# Control.net
KiCad netlist of a schematic drawn in Altium Designer
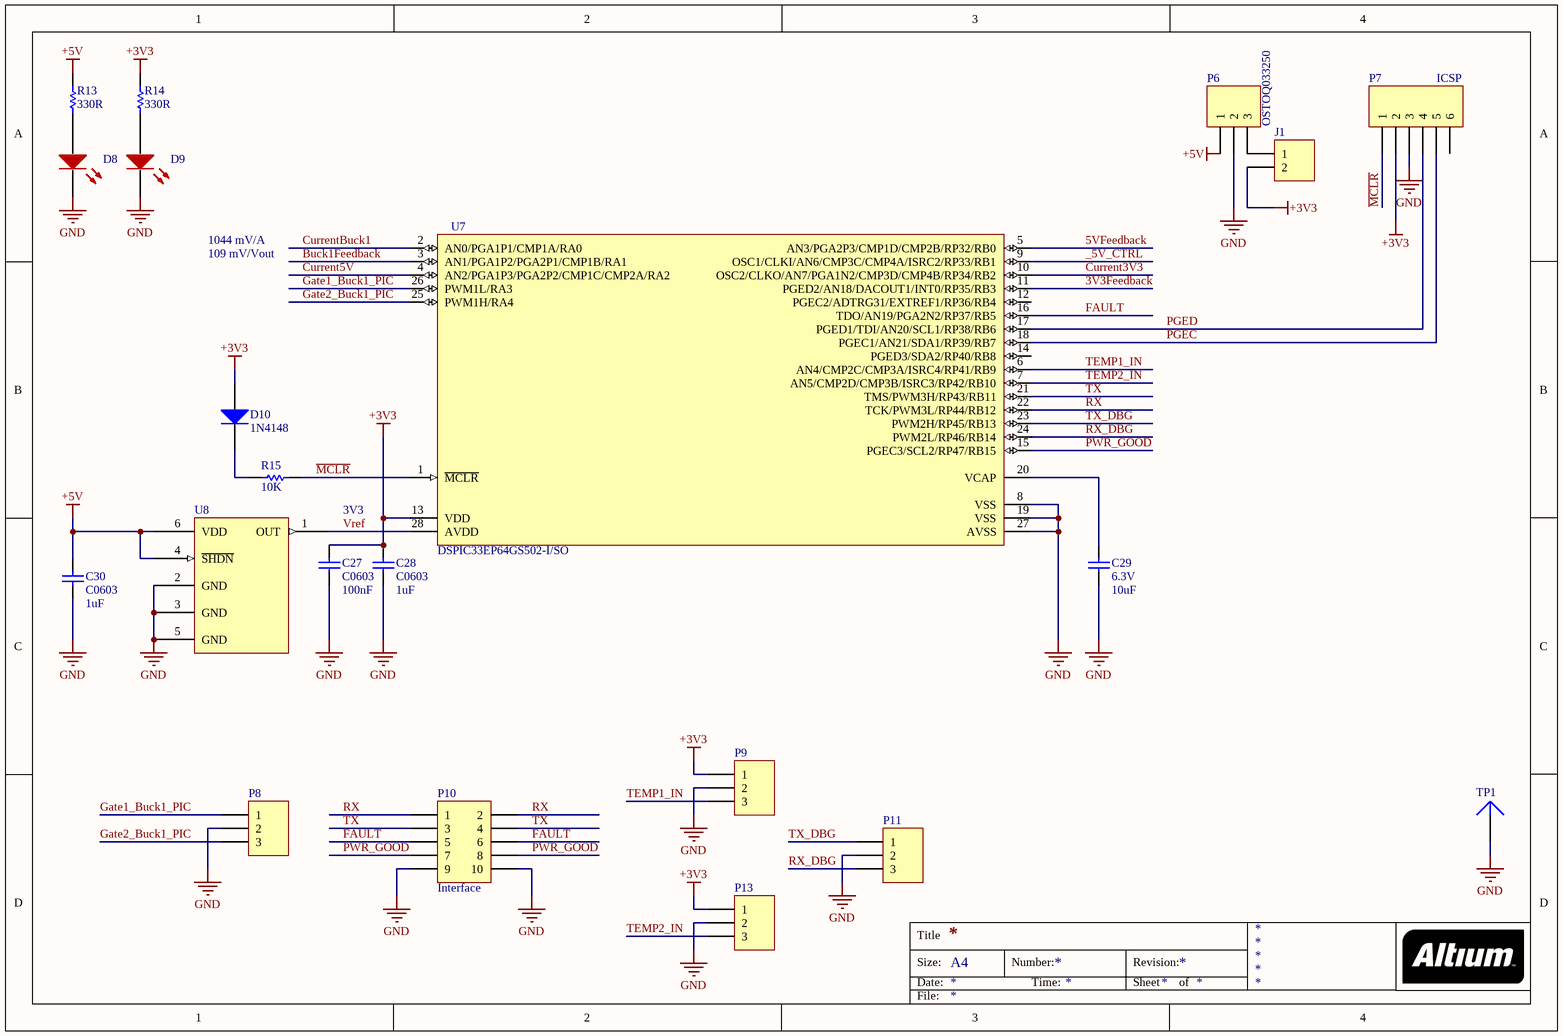
[diagram p0: Control.SchDoc]

(export (version "E")
  (design (tool "Eeschema 10.0.6"))
  (components
    (comp (ref "C27")
      (value "C0603")
      (footprint "0603")
      (description "C1608X7R1C105K X7R")
      (fields (field (name "ALTIUM_VALUE") "100nF") (field (name "PUBLISHER") "Altium Limited"))
      (libsource (lib "KEMET Chip Capacitor") (part "C0603"))
    )
    (comp (ref "C28")
      (value "C0603")
      (footprint "0603")
      (description "C1608X7R1C105K X7R")
      (fields (field (name "ALTIUM_VALUE") "1uF") (field (name "PUBLISHER") "Altium Limited"))
      (libsource (lib "KEMET Chip Capacitor") (part "C0603"))
    )
    (comp (ref "C29")
      (value "6.3V")
      (footprint "C0805")
      (description "Ceramic Chip Capacitor - MIL-PRF-55681")
      (fields (field (name "ALTIUM_VALUE") "10uF") (field (name "PUBLISHER") "Altium Limited"))
      (libsource (lib "KEMET Chip Capacitor") (part "CDR01"))
    )
    (comp (ref "C30")
      (value "C0603")
      (footprint "0603")
      (description "C1608X7R1C105K X7R")
      (fields (field (name "ALTIUM_VALUE") "1uF") (field (name "PUBLISHER") "Altium Limited"))
      (libsource (lib "KEMET Chip Capacitor") (part "C0603"))
    )
    (comp (ref "D8")
      (value "15-21SURC/S530-A3/TR8")
      (footprint "15-21SURC/S530-A3/TR8")
      (description "15-21SURC/S530-A3/TR8 led smd 0805 red")
      (libsource (lib "NXT") (part "15-21SURC/S530-A3/TR8 led smd 0805 red"))
    )
    (comp (ref "D9")
      (value "15-21SURC/S530-A3/TR8")
      (footprint "15-21SURC/S530-A3/TR8")
      (description "15-21SURC/S530-A3/TR8 led smd 0805 red")
      (libsource (lib "NXT") (part "15-21SURC/S530-A3/TR8 led smd 0805 red"))
    )
    (comp (ref "D10")
      (value "1N4148")
      (footprint "Philips Discrete Diode - Switching:SOD80C")
      (description "High Conductance Fast Diode")
      (fields (field (name "PUBLISHER") "Altium Limited"))
      (libsource (lib "FSC Discrete Diode") (part "1N4148"))
    )
    (comp (ref "J1")
      (value "Header 2")
      (footprint "My_1X02")
      (description "Header, 2-Pin")
      (fields (field (name "PUBLISHER") "Altium Limited"))
      (libsource (lib "Mylib") (part "Header 2"))
    )
    (comp (ref "P6")
      (value "XY2500R-F 3P")
      (footprint "OSTOQ033250")
      (description "HEADER 3P P/CI 90gra VERDE P=3.81MM XY2500R-F")
      (fields
        (field (name "MANUFACTURER") "On Shore Technology Inc.")
        (field (name "MANUFACTURER PART NUMBER") "OSTOQ033250")
      )
      (libsource (lib "NXT - Connectors") (part "XY2500R-F 3P"))
    )
    (comp (ref "P7")
      (value "ICSP")
      (footprint "My_1X06")
      (description "Header, 6-Pin")
      (fields (field (name "PUBLISHER") "Altium Limited"))
      (libsource (lib "Mylib") (part "Header 6"))
    )
    (comp (ref "P8")
      (value "Header 3")
      (footprint "My_1X03")
      (description "Header, 3-Pin")
      (fields (field (name "PUBLISHER") "Altium Limited"))
      (libsource (lib "Mylib") (part "Header 3"))
    )
    (comp (ref "P9")
      (value "Header 3")
      (footprint "My_1X03")
      (description "Header, 3-Pin")
      (fields (field (name "PUBLISHER") "Altium Limited"))
      (libsource (lib "Mylib") (part "Header 3"))
    )
    (comp (ref "P10")
      (value "Interface")
      (footprint "HDR2X5")
      (description "Header, 5-Pin, Dual row")
      (fields (field (name "PUBLISHER") "Altium Limited"))
      (libsource (lib "Miscellaneous Connectors") (part "Header 5X2"))
    )
    (comp (ref "P11")
      (value "Header 3")
      (footprint "My_1X03")
      (description "Header, 3-Pin")
      (fields (field (name "PUBLISHER") "Altium Limited"))
      (libsource (lib "Mylib") (part "Header 3"))
    )
    (comp (ref "P13")
      (value "Header 3")
      (footprint "My_1X03")
      (description "Header, 3-Pin")
      (fields (field (name "PUBLISHER") "Altium Limited"))
      (libsource (lib "Mylib") (part "Header 3"))
    )
    (comp (ref "R13")
      (value "330R")
      (footprint "8RB-1206")
      (fields (field (name "Comment") "SMD") (field (name "PUBLISHER") "Altium Limited"))
      (libsource (lib "Panasonic Resistor") (part "ERJ8BQ"))
    )
    (comp (ref "R14")
      (value "330R")
      (footprint "8RB-1206")
      (fields (field (name "Comment") "SMD") (field (name "PUBLISHER") "Altium Limited"))
      (libsource (lib "Panasonic Resistor") (part "ERJ8BQ"))
    )
    (comp (ref "R15")
      (value "10K")
      (footprint "ERA-0603")
      (fields (field (name "PUBLISHER") "Altium Limited"))
      (libsource (lib "Panasonic Resistor") (part "ERA3Y"))
    )
    (comp (ref "TP1")
      (value "~")
      (footprint "PIN1")
      (description "Plug")
      (fields (field (name "PUBLISHER") "Altium Limited"))
      (libsource (lib "Miscellaneous Connectors") (part "Plug"))
    )
    (comp (ref "U7")
      (value "DSPIC33EP64GS502")
      (footprint "MCHP-SOIC-SO28_N")
      (description "dsPIC dsPIC™ 33EP Microcontroller IC 16-Bit 70 MIPs 64KB (64K x 8) FLASH 28-SOIC")
      (fields
        (field (name "MANUFACTURER") "Microchip Technology")
        (field (name "MANUFACTURER PART NUMBER") "DSPIC33EP64GS502-I/SO")
      )
      (libsource (lib "NXT - IC") (part "DSPIC33EP64GS502"))
    )
    (comp (ref "U8")
      (value "MCP1501T")
      (footprint "SOT-23-6")
      (description "Series Voltage Reference IC ±0.08% 20mA SOT-23-6")
      (libsource (lib "NXT - IC") (part "MCP1501T"))
    )
  )
  (nets
    (net (code "1") (name "+3V3") (class "Default")
      (node (ref "C27") (pin "1") (pinfunction "1_1") (pintype "passive"))
      (node (ref "C28") (pin "1") (pinfunction "1_1") (pintype "passive"))
      (node (ref "D10") (pin "1") (pinfunction "A_1") (pintype "passive"))
      (node (ref "J1") (pin "2") (pinfunction "2_2") (pintype "passive"))
      (node (ref "P13") (pin "1") (pinfunction "1_1") (pintype "passive"))
      (node (ref "P7") (pin "2") (pinfunction "2_2") (pintype "passive"))
      (node (ref "P9") (pin "1") (pinfunction "1_1") (pintype "passive"))
      (node (ref "R14") (pin "1") (pinfunction "1_1") (pintype "passive"))
      (node (ref "U7") (pin "13") (pinfunction "VDD_13") (pintype "power_in"))
    )
    (net (code "2") (name "+5V") (class "Default")
      (node (ref "C30") (pin "1") (pinfunction "1_1") (pintype "passive"))
      (node (ref "P6") (pin "1") (pinfunction "1_1") (pintype "passive"))
      (node (ref "R13") (pin "1") (pinfunction "1_1") (pintype "passive"))
      (node (ref "U8") (pin "4") (pinfunction "~{SHDN}_4") (pintype "input"))
      (node (ref "U8") (pin "6") (pinfunction "VDD_6") (pintype "power_in"))
    )
    (net (code "3") (name "/3V3Feedback") (class "Default")
      (node (ref "U7") (pin "11") (pinfunction "PGED2/AN18/DACOUT1/INT0/RP35/RB3_11") (pintype "bidirectional"))
    )
    (net (code "4") (name "/5VFeedback") (class "Default")
      (node (ref "U7") (pin "5") (pinfunction "AN3/PGA2P3/CMP1D/CMP2B/RP32/RB0_5") (pintype "bidirectional"))
    )
    (net (code "5") (name "/Buck1Feedback") (class "Default")
      (node (ref "U7") (pin "3") (pinfunction "AN1/PGA1P2/PGA2P1/CMP1B/RA1_3") (pintype "bidirectional"))
    )
    (net (code "6") (name "/Current3V3") (class "Default")
      (node (ref "U7") (pin "10") (pinfunction "OSC2/CLKO/AN7/PGA1N2/CMP3D/CMP4B/RP34/RB2_10") (pintype "bidirectional"))
    )
    (net (code "7") (name "/Current5V") (class "Default")
      (node (ref "U7") (pin "4") (pinfunction "AN2/PGA1P3/PGA2P2/CMP1C/CMP2A/RA2_4") (pintype "bidirectional"))
    )
    (net (code "8") (name "/CurrentBuck1") (class "Default")
      (node (ref "U7") (pin "2") (pinfunction "AN0/PGA1P1/CMP1A/RA0_2") (pintype "bidirectional"))
    )
    (net (code "9") (name "/FAULT") (class "Default")
      (node (ref "P10") (pin "5") (pinfunction "5_5") (pintype "passive"))
      (node (ref "P10") (pin "6") (pinfunction "6_6") (pintype "passive"))
      (node (ref "U7") (pin "16") (pinfunction "TDO/AN19/PGA2N2/RP37/RB5_16") (pintype "bidirectional"))
    )
    (net (code "10") (name "/Gate1_Buck1_PIC") (class "Default")
      (node (ref "P8") (pin "1") (pinfunction "1_1") (pintype "passive"))
      (node (ref "U7") (pin "26") (pinfunction "PWM1L/RA3_26") (pintype "bidirectional"))
    )
    (net (code "11") (name "/Gate2_Buck1_PIC") (class "Default")
      (node (ref "P8") (pin "3") (pinfunction "3_3") (pintype "passive"))
      (node (ref "U7") (pin "25") (pinfunction "PWM1H/RA4_25") (pintype "bidirectional"))
    )
    (net (code "12") (name "/PGEC") (class "Default")
      (node (ref "P7") (pin "5") (pinfunction "5_5") (pintype "passive"))
      (node (ref "U7") (pin "18") (pinfunction "PGEC1/AN21/SDA1/RP39/RB7_18") (pintype "bidirectional"))
    )
    (net (code "13") (name "/PGED") (class "Default")
      (node (ref "P7") (pin "4") (pinfunction "4_4") (pintype "passive"))
      (node (ref "U7") (pin "17") (pinfunction "PGED1/TDI/AN20/SCL1/RP38/RB6_17") (pintype "bidirectional"))
    )
    (net (code "14") (name "/PWR_GOOD") (class "Default")
      (node (ref "P10") (pin "7") (pinfunction "7_7") (pintype "passive"))
      (node (ref "P10") (pin "8") (pinfunction "8_8") (pintype "passive"))
      (node (ref "U7") (pin "15") (pinfunction "PGEC3/SCL2/RP47/RB15_15") (pintype "bidirectional"))
    )
    (net (code "15") (name "/RX") (class "Default")
      (node (ref "P10") (pin "1") (pinfunction "1_1") (pintype "passive"))
      (node (ref "P10") (pin "2") (pinfunction "2_2") (pintype "passive"))
      (node (ref "U7") (pin "22") (pinfunction "TCK/PWM3L/RP44/RB12_22") (pintype "bidirectional"))
    )
    (net (code "16") (name "/RX_DBG") (class "Default")
      (node (ref "P11") (pin "3") (pinfunction "3_3") (pintype "passive"))
      (node (ref "U7") (pin "24") (pinfunction "PWM2L/RP46/RB14_24") (pintype "bidirectional"))
    )
    (net (code "17") (name "/TEMP1_IN") (class "Default")
      (node (ref "P9") (pin "3") (pinfunction "3_3") (pintype "passive"))
      (node (ref "U7") (pin "6") (pinfunction "AN4/CMP2C/CMP3A/ISRC4/RP41/RB9_6") (pintype "bidirectional"))
    )
    (net (code "18") (name "/TEMP2_IN") (class "Default")
      (node (ref "P13") (pin "3") (pinfunction "3_3") (pintype "passive"))
      (node (ref "U7") (pin "7") (pinfunction "AN5/CMP2D/CMP3B/ISRC3/RP42/RB10_7") (pintype "bidirectional"))
    )
    (net (code "19") (name "/TX") (class "Default")
      (node (ref "P10") (pin "3") (pinfunction "3_3") (pintype "passive"))
      (node (ref "P10") (pin "4") (pinfunction "4_4") (pintype "passive"))
      (node (ref "U7") (pin "21") (pinfunction "TMS/PWM3H/RP43/RB11_21") (pintype "bidirectional"))
    )
    (net (code "20") (name "/TX_DBG") (class "Default")
      (node (ref "P11") (pin "1") (pinfunction "1_1") (pintype "passive"))
      (node (ref "U7") (pin "23") (pinfunction "PWM2H/RP45/RB13_23") (pintype "bidirectional"))
    )
    (net (code "21") (name "/Vref") (class "Default")
      (node (ref "U7") (pin "28") (pinfunction "AVDD_28") (pintype "power_in"))
      (node (ref "U8") (pin "1") (pinfunction "OUT_1") (pintype "output"))
    )
    (net (code "22") (name "/_5V_CTRL") (class "Default")
      (node (ref "U7") (pin "9") (pinfunction "OSC1/CLKI/AN6/CMP3C/CMP4A/ISRC2/RP33/RB1_9") (pintype "bidirectional"))
    )
    (net (code "23") (name "/~{MCLR}") (class "Default")
      (node (ref "P7") (pin "1") (pinfunction "1_1") (pintype "passive"))
      (node (ref "R15") (pin "1") (pinfunction "1_1") (pintype "passive"))
      (node (ref "U7") (pin "1") (pinfunction "~{MCLR}_1") (pintype "input"))
    )
    (net (code "24") (name "GND") (class "Default")
      (node (ref "C27") (pin "2") (pinfunction "2_2") (pintype "passive"))
      (node (ref "C28") (pin "2") (pinfunction "2_2") (pintype "passive"))
      (node (ref "C29") (pin "1") (pinfunction "1_1") (pintype "passive"))
      (node (ref "C30") (pin "2") (pinfunction "2_2") (pintype "passive"))
      (node (ref "D8") (pin "2") (pinfunction "2_2") (pintype "passive"))
      (node (ref "D9") (pin "2") (pinfunction "2_2") (pintype "passive"))
      (node (ref "P10") (pin "10") (pinfunction "10_10") (pintype "passive"))
      (node (ref "P10") (pin "9") (pinfunction "9_9") (pintype "passive"))
      (node (ref "P11") (pin "2") (pinfunction "2_2") (pintype "passive"))
      (node (ref "P13") (pin "2") (pinfunction "2_2") (pintype "passive"))
      (node (ref "P6") (pin "2") (pinfunction "2_2") (pintype "passive"))
      (node (ref "P7") (pin "3") (pinfunction "3_3") (pintype "passive"))
      (node (ref "P8") (pin "2") (pinfunction "2_2") (pintype "passive"))
      (node (ref "P9") (pin "2") (pinfunction "2_2") (pintype "passive"))
      (node (ref "TP1") (pin "1") (pinfunction "1_1") (pintype "passive"))
      (node (ref "U7") (pin "19") (pinfunction "VSS_19") (pintype "power_in"))
      (node (ref "U7") (pin "27") (pinfunction "AVSS_27") (pintype "power_in"))
      (node (ref "U7") (pin "8") (pinfunction "VSS_8") (pintype "power_in"))
      (node (ref "U8") (pin "2") (pinfunction "GND_2") (pintype "power_in"))
      (node (ref "U8") (pin "3") (pinfunction "GND_3") (pintype "power_in"))
      (node (ref "U8") (pin "5") (pinfunction "GND_5") (pintype "power_in"))
    )
    (net (code "25") (name "Net-(D8-Pad1)") (class "Default")
      (node (ref "D8") (pin "1") (pinfunction "1_1") (pintype "passive"))
      (node (ref "R13") (pin "2") (pinfunction "2_2") (pintype "passive"))
    )
    (net (code "26") (name "Net-(D9-Pad1)") (class "Default")
      (node (ref "D9") (pin "1") (pinfunction "1_1") (pintype "passive"))
      (node (ref "R14") (pin "2") (pinfunction "2_2") (pintype "passive"))
    )
    (net (code "27") (name "Net-(D10-K)") (class "Default")
      (node (ref "D10") (pin "2") (pinfunction "K_2") (pintype "passive"))
      (node (ref "R15") (pin "2") (pinfunction "2_2") (pintype "passive"))
    )
    (net (code "28") (name "Net-(J1-Pad1)") (class "Default")
      (node (ref "J1") (pin "1") (pinfunction "1_1") (pintype "passive"))
      (node (ref "P6") (pin "3") (pinfunction "3_3") (pintype "passive"))
    )
    (net (code "29") (name "Net-(U7-VCAP)") (class "Default")
      (node (ref "C29") (pin "2") (pinfunction "2_2") (pintype "passive"))
      (node (ref "U7") (pin "20") (pinfunction "VCAP_20") (pintype "passive"))
    )
    (net (code "30") (name "unconnected-(P7-Pad6)") (class "Default")
      (node (ref "P7") (pin "6") (pinfunction "6_6") (pintype "passive"))
    )
    (net (code "31") (name "unconnected-(U7-PGEC2{slash}ADTRG31{slash}EXTREF1{slash}RP36{slash}RB4-Pad12)") (class "Default")
      (node (ref "U7") (pin "12") (pinfunction "PGEC2/ADTRG31/EXTREF1/RP36/RB4_12") (pintype "bidirectional"))
    )
    (net (code "32") (name "unconnected-(U7-PGED3{slash}SDA2{slash}RP40{slash}RB8-Pad14)") (class "Default")
      (node (ref "U7") (pin "14") (pinfunction "PGED3/SDA2/RP40/RB8_14") (pintype "bidirectional"))
    )
  )
)
